# IMU.net
KiCad netlist of a schematic drawn in Altium Designer
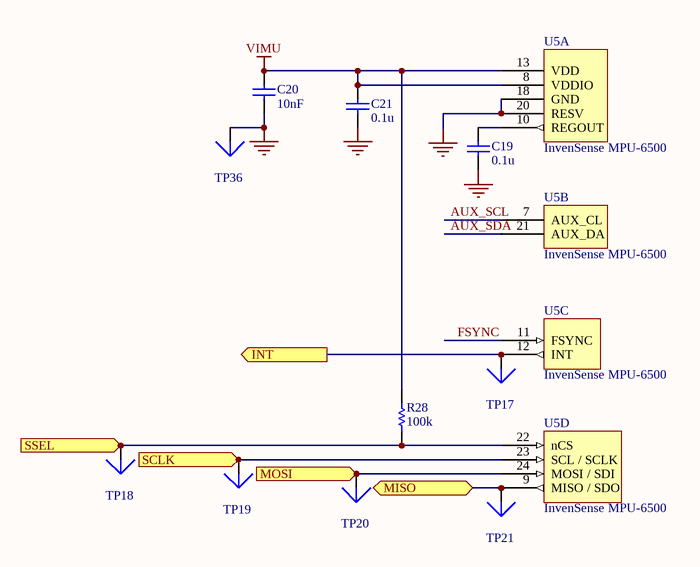
[diagram p0: IMU.SchDoc]

(export (version "E")
  (design (tool "Eeschema 10.0.6"))
  (components
    (comp (ref "C19")
      (value "0.1u")
      (footprint "CAP0201")
      (description "Chip capacitor")
      (fields (field (name "TOLERANCE") "10%") (field (name "VOLTAGE") "10V"))
      (libsource (lib "Hello") (part "C_0.1u_10_10_X5R_0201"))
    )
    (comp (ref "C20")
      (value "10nF")
      (footprint "CAP0201")
      (description "Chip capacitor")
      (fields (field (name "VOLTAGE") "6.3v") (field (name "TOLERANCE") "10%"))
      (libsource (lib "Hello") (part "CAP0201"))
    )
    (comp (ref "C21")
      (value "0.1u")
      (footprint "CAP0201")
      (description "Chip capacitor")
      (fields (field (name "TOLERANCE") "10%") (field (name "VOLTAGE") "10V"))
      (libsource (lib "Hello") (part "C_0.1u_10_10_X5R_0201"))
    )
    (comp (ref "R28")
      (value "100k")
      (footprint "RES0201")
      (description "Chip Resistor")
      (fields (field (name "TOLERANCE") "5 %") (field (name "POWER") "0.05 W"))
      (libsource (lib "Hello") (part "R_100k_5_0.05_0201"))
    )
    (comp (ref "TP17")
      (value "TestPoint")
      (footprint "TP-0.3")
      (description "Generic Test Point")
      (libsource (lib "Hello") (part "TestPoint"))
    )
    (comp (ref "TP18")
      (value "TestPoint")
      (footprint "TP-0.3")
      (description "Generic Test Point")
      (libsource (lib "Hello") (part "TestPoint"))
    )
    (comp (ref "TP19")
      (value "TestPoint")
      (footprint "TP-0.3")
      (description "Generic Test Point")
      (libsource (lib "Hello") (part "TestPoint"))
    )
    (comp (ref "TP20")
      (value "TestPoint")
      (footprint "TP-0.3")
      (description "Generic Test Point")
      (libsource (lib "Hello") (part "TestPoint"))
    )
    (comp (ref "TP21")
      (value "TestPoint")
      (footprint "TP-0.3")
      (description "Generic Test Point")
      (libsource (lib "Hello") (part "TestPoint"))
    )
    (comp (ref "TP36")
      (value "TestPoint")
      (footprint "TP-0.3")
      (description "Generic Test Point")
      (libsource (lib "Hello") (part "TestPoint"))
    )
    (comp (ref "U5")
      (value "InvenSense MPU-6500")
      (footprint "QFN-24")
      (description "InvenSense MPU-6500 6-axis accelerometer and gyroscope")
      (libsource (lib "Hello") (part "MPU-6500"))
    )
  )
  (nets
    (net (code "1") (name "/AUX_SCL") (class "Default")
      (node (ref "U5") (pin "7") (pinfunction "AUX_CL_7") (pintype "passive"))
    )
    (net (code "2") (name "/AUX_SDA") (class "Default")
      (node (ref "U5") (pin "21") (pinfunction "AUX_DA_21") (pintype "passive"))
    )
    (net (code "3") (name "/FSYNC") (class "Default")
      (node (ref "U5") (pin "11") (pinfunction "FSYNC_11") (pintype "input"))
    )
    (net (code "4") (name "/INT") (class "Default")
      (node (ref "TP17") (pin "1") (pinfunction "1_1") (pintype "passive"))
      (node (ref "U5") (pin "12") (pinfunction "INT_12") (pintype "output"))
    )
    (net (code "5") (name "/MISO") (class "Default")
      (node (ref "TP21") (pin "1") (pinfunction "1_1") (pintype "passive"))
      (node (ref "U5") (pin "9") (pinfunction "MISO_/_SDO_9") (pintype "output"))
    )
    (net (code "6") (name "/MOSI") (class "Default")
      (node (ref "TP20") (pin "1") (pinfunction "1_1") (pintype "passive"))
      (node (ref "U5") (pin "24") (pinfunction "MOSI_/_SDI_24") (pintype "input"))
    )
    (net (code "7") (name "/SCLK") (class "Default")
      (node (ref "TP19") (pin "1") (pinfunction "1_1") (pintype "passive"))
      (node (ref "U5") (pin "23") (pinfunction "SCL_/_SCLK_23") (pintype "input"))
    )
    (net (code "8") (name "/SSEL") (class "Default")
      (node (ref "R28") (pin "1") (pinfunction "1_1") (pintype "passive"))
      (node (ref "TP18") (pin "1") (pinfunction "1_1") (pintype "passive"))
      (node (ref "U5") (pin "22") (pinfunction "nCS_22") (pintype "input"))
    )
    (net (code "9") (name "GND") (class "Default")
      (node (ref "C19") (pin "1") (pinfunction "1_1") (pintype "passive"))
      (node (ref "C20") (pin "1") (pinfunction "1_1") (pintype "passive"))
      (node (ref "C21") (pin "1") (pinfunction "1_1") (pintype "passive"))
      (node (ref "TP36") (pin "1") (pinfunction "1_1") (pintype "passive"))
      (node (ref "U5") (pin "18") (pinfunction "GND_18") (pintype "power_in"))
      (node (ref "U5") (pin "20") (pinfunction "RESV_20") (pintype "passive"))
    )
    (net (code "10") (name "Net-(U5A-REGOUT)") (class "Default")
      (node (ref "C19") (pin "2") (pinfunction "2_2") (pintype "passive"))
      (node (ref "U5") (pin "10") (pinfunction "REGOUT_10") (pintype "output"))
    )
    (net (code "11") (name "VIMU") (class "Default")
      (node (ref "C20") (pin "2") (pinfunction "2_2") (pintype "passive"))
      (node (ref "C21") (pin "2") (pinfunction "2_2") (pintype "passive"))
      (node (ref "R28") (pin "2") (pinfunction "2_2") (pintype "passive"))
      (node (ref "U5") (pin "13") (pinfunction "VDD_13") (pintype "power_in"))
      (node (ref "U5") (pin "8") (pinfunction "VDDIO_8") (pintype "power_in"))
    )
  )
)
